# TeensyCtrlr.net
KiCad netlist of a schematic drawn in EAGLE
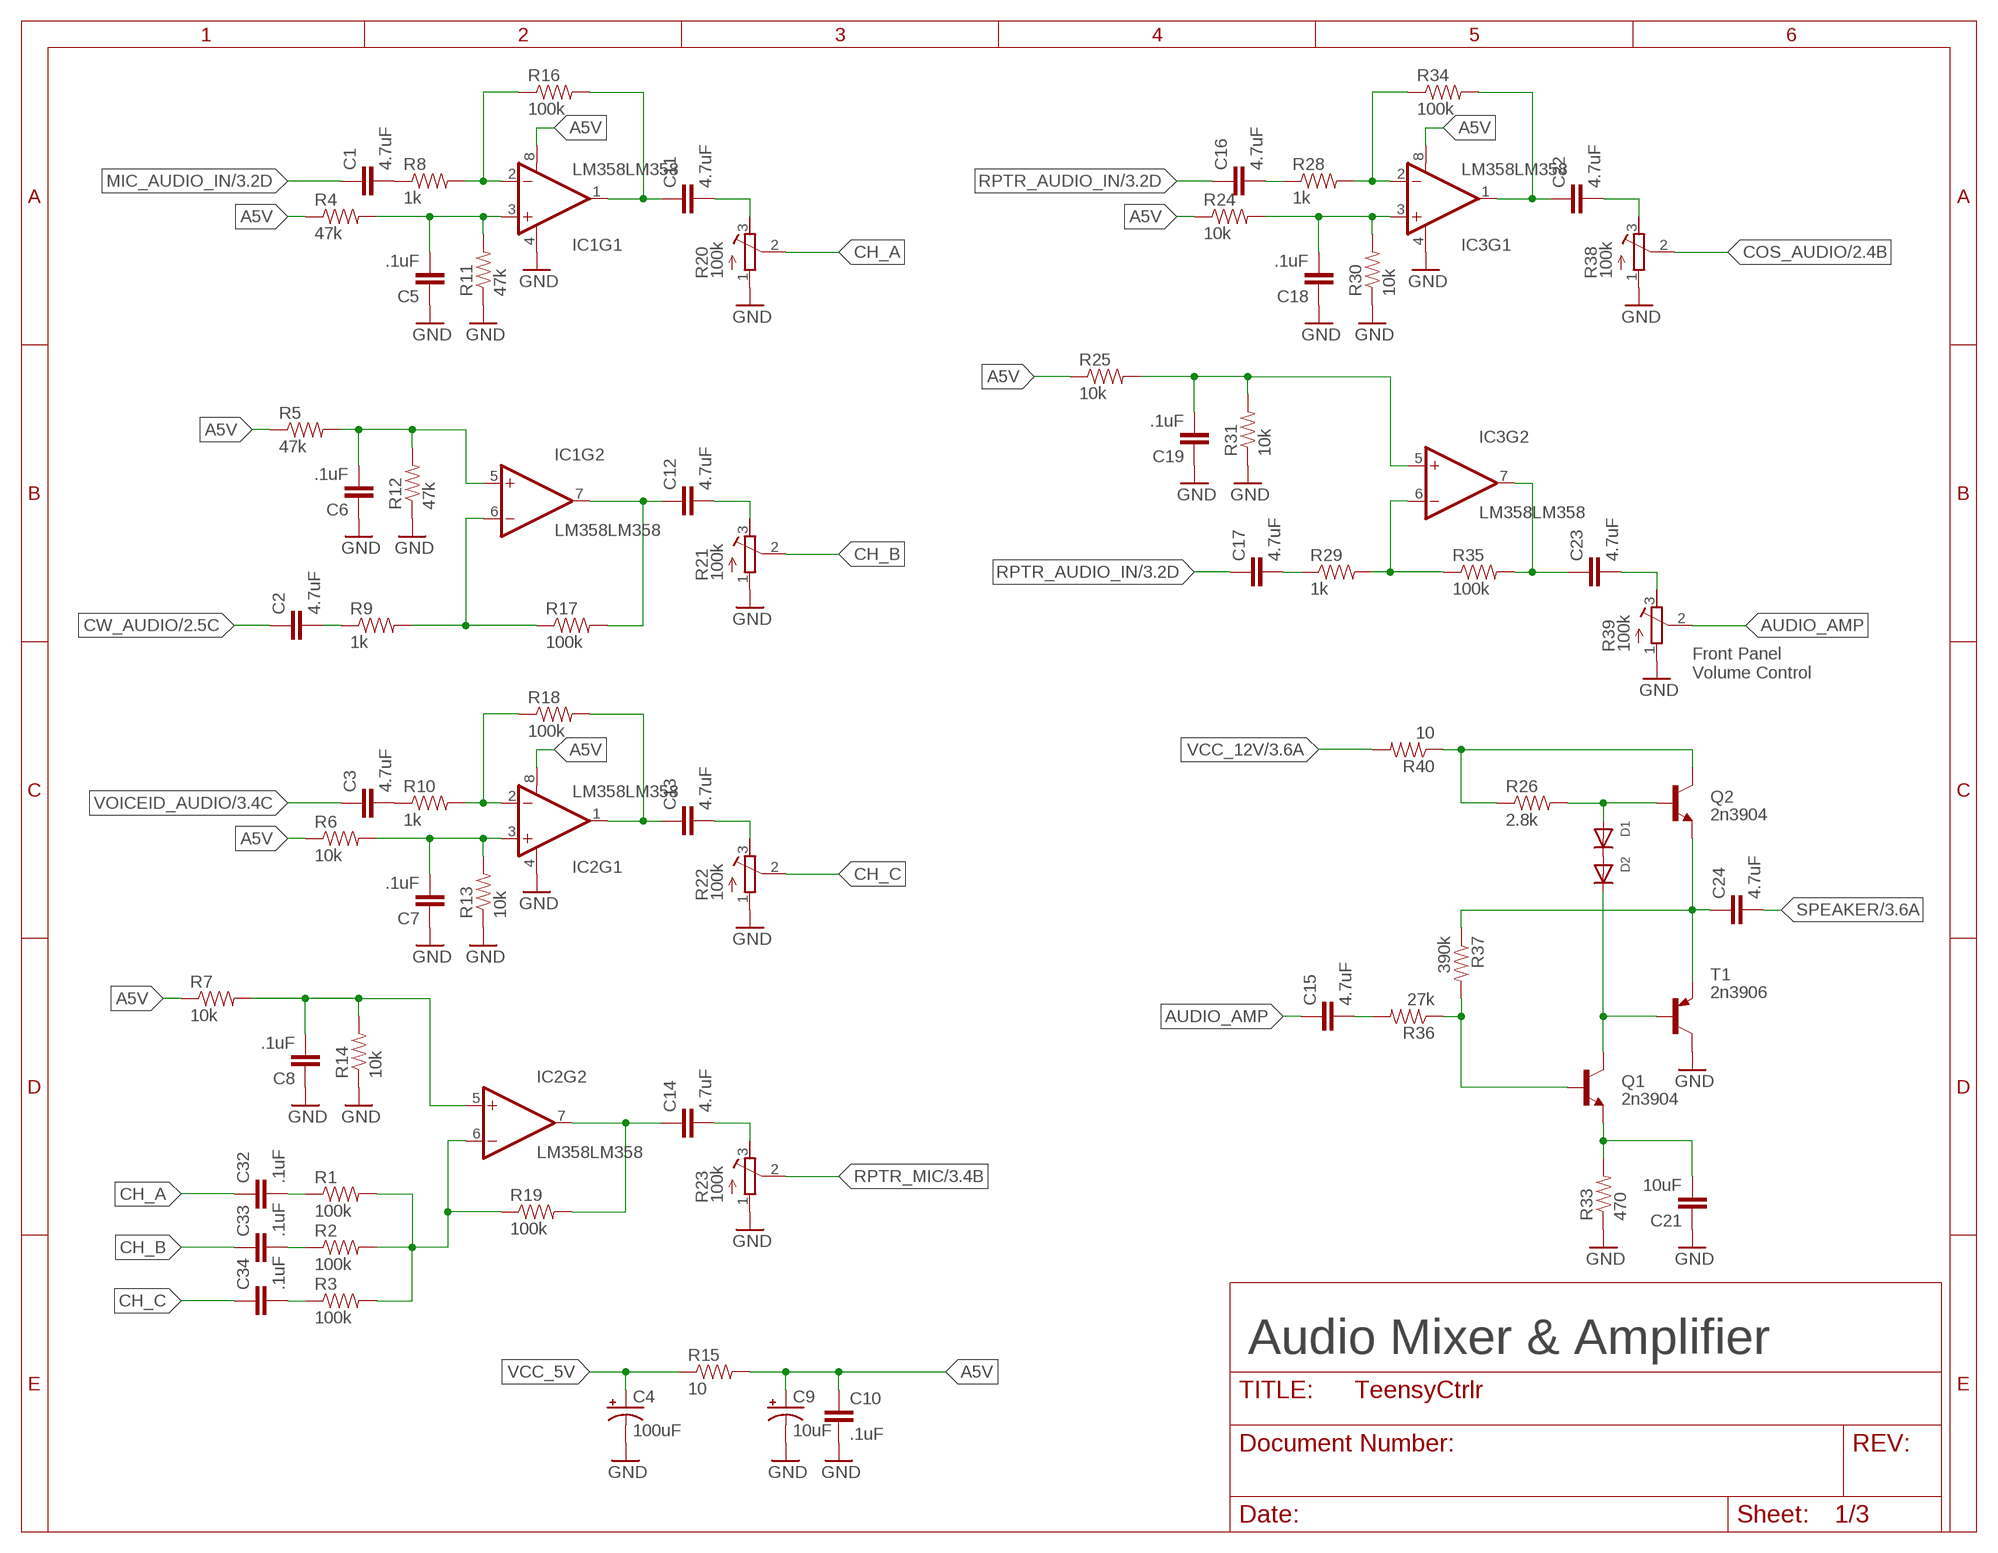
[diagram p0: schematic, sheet 1]
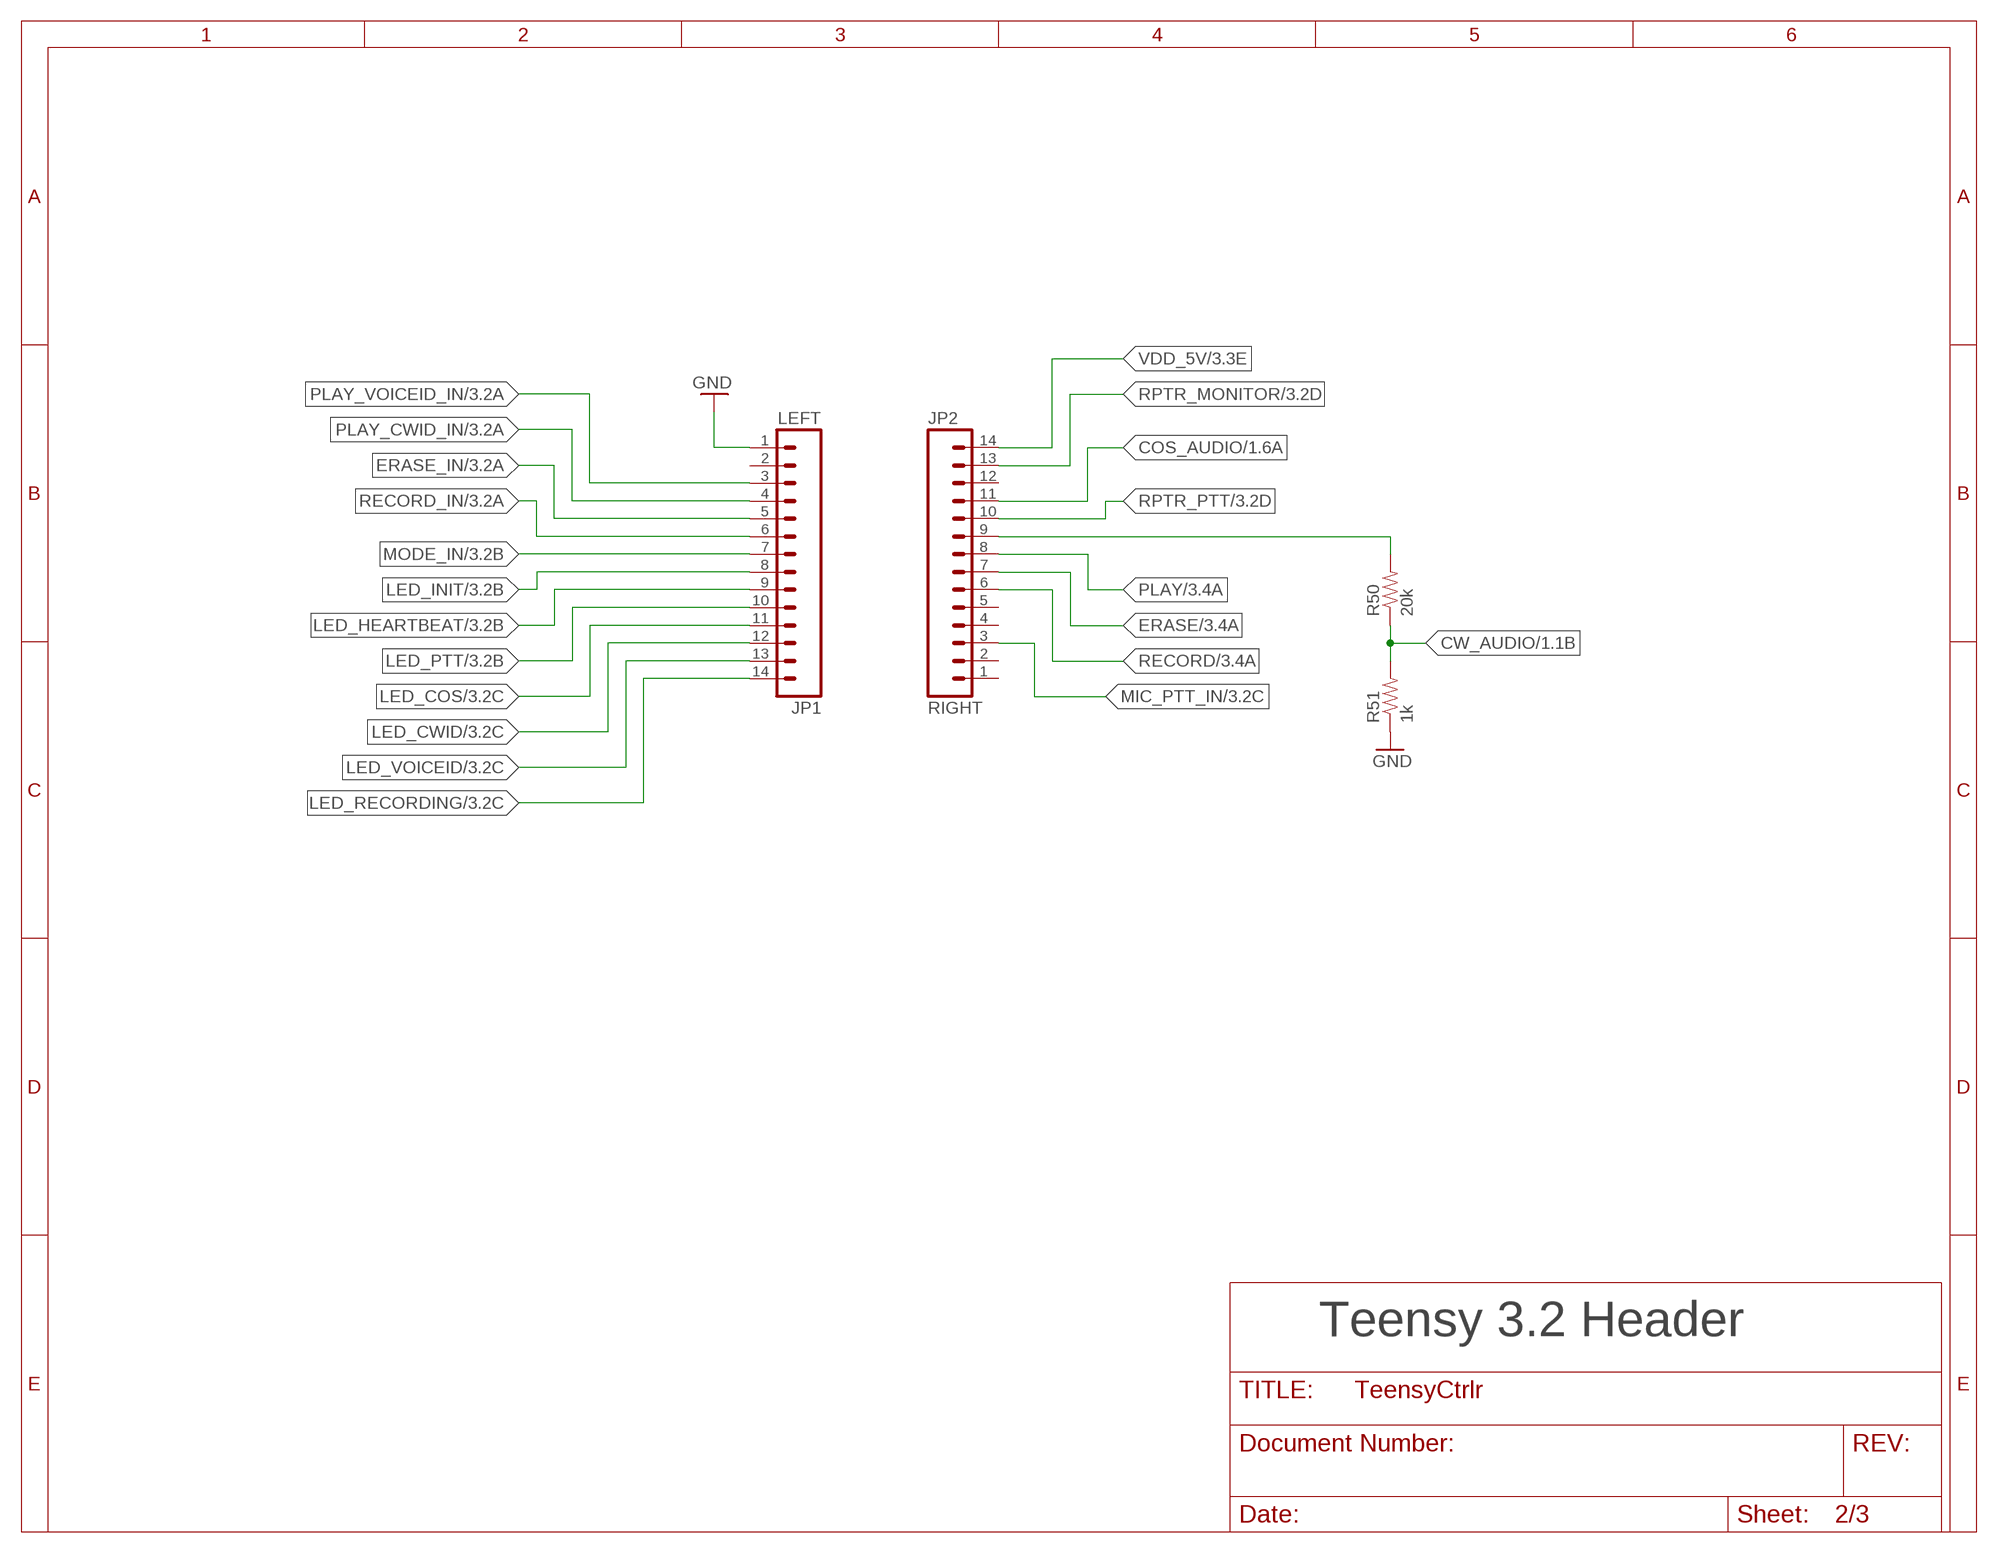
[diagram p1: schematic, sheet 2]
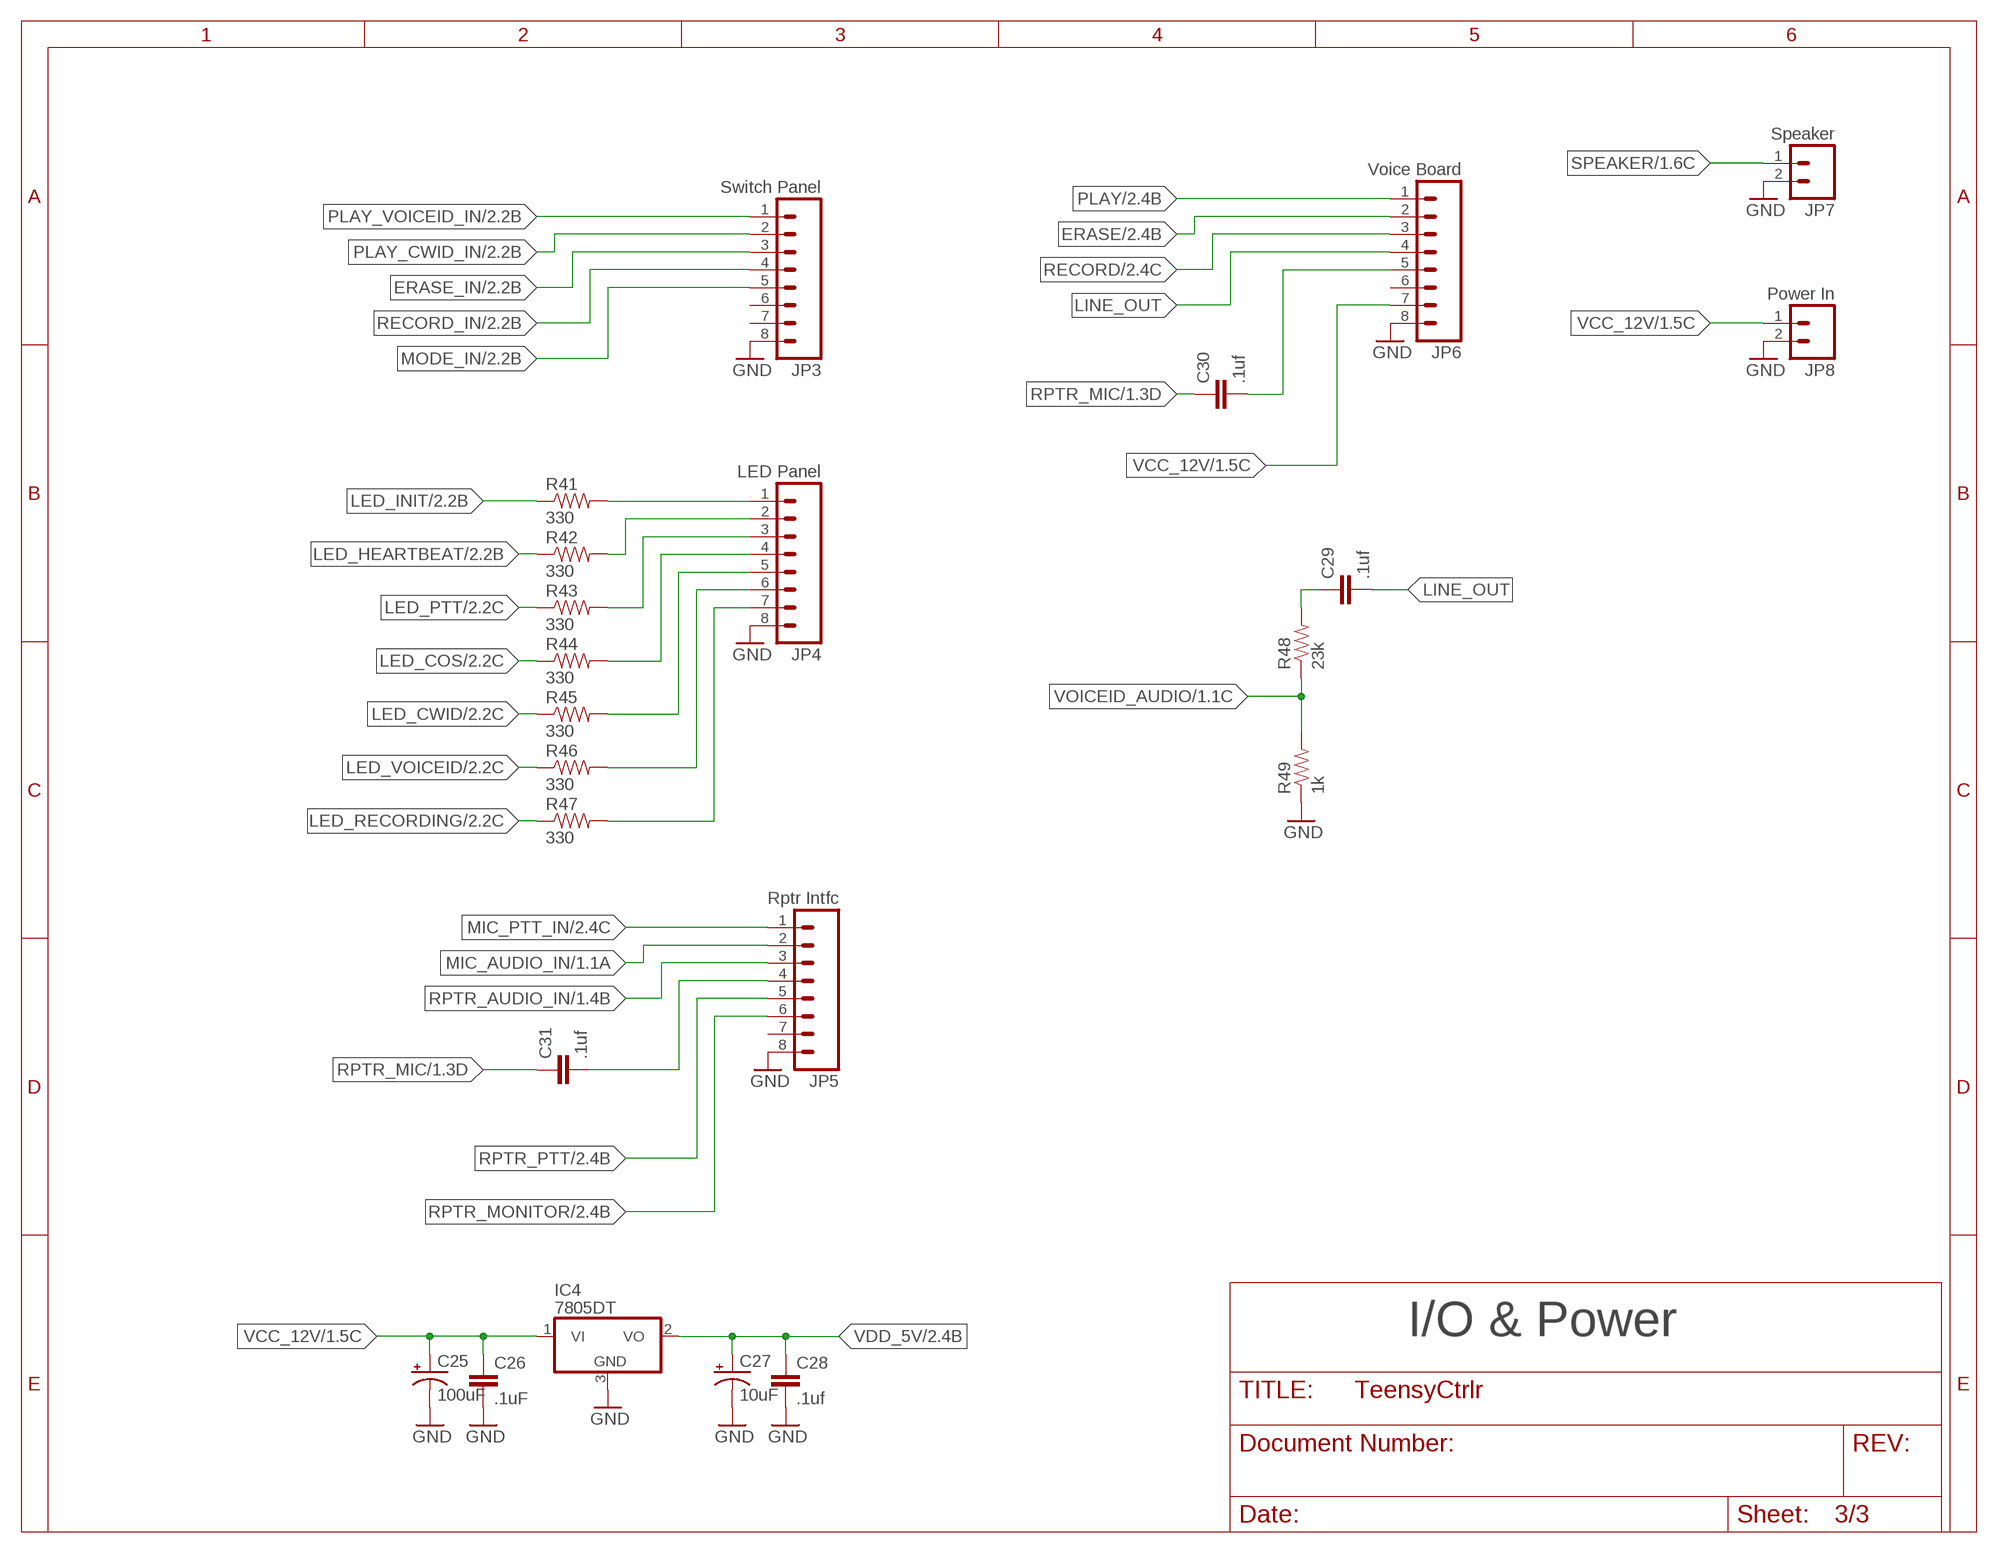
[diagram p2: schematic, sheet 3]

(export (version "E")
  (design (tool "Eeschema 10.0.6"))
  (components
    (comp (ref "C25")
      (value "100uF")
      (footprint "eagle-import:CPOL-RADIAL-1000UF-25V")
      (libsource (lib "eagle-import") (part "CAP_POLPTH4"))
    )
    (comp (ref "C26")
      (value ".1uF")
      (footprint "eagle-import:0805")
      (libsource (lib "eagle-import") (part "CAP0805"))
    )
    (comp (ref "C27")
      (value "10uF")
      (footprint "eagle-import:CPOL-RADIAL-100UF-25V")
      (libsource (lib "eagle-import") (part "CAP_POLPTH1"))
    )
    (comp (ref "C28")
      (value ".1uf")
      (footprint "eagle-import:0805")
      (libsource (lib "eagle-import") (part "CAP0805"))
    )
    (comp (ref "C29")
      (value ".1uf")
      (footprint "eagle-import:0805")
      (libsource (lib "eagle-import") (part "CAP0805"))
    )
    (comp (ref "C30")
      (value ".1uf")
      (footprint "eagle-import:0805")
      (libsource (lib "eagle-import") (part "CAP0805"))
    )
    (comp (ref "C31")
      (value ".1uf")
      (footprint "eagle-import:0805")
      (libsource (lib "eagle-import") (part "CAP0805"))
    )
    (comp (ref "IC4")
      (value "7805DT")
      (footprint "eagle-import:TO252")
      (libsource (lib "eagle-import") (part "78DT05"))
    )
    (comp (ref "JP3")
      (value "Switch Panel")
      (footprint "eagle-import:1X08_LONGPADS")
      (libsource (lib "eagle-import") (part "M08LONGPADS"))
    )
    (comp (ref "JP4")
      (value "LED Panel")
      (footprint "eagle-import:1X08_LONGPADS")
      (libsource (lib "eagle-import") (part "M08LONGPADS"))
    )
    (comp (ref "JP5")
      (value "Rptr Intfc")
      (footprint "eagle-import:1X08_LONGPADS")
      (libsource (lib "eagle-import") (part "M08LONGPADS"))
    )
    (comp (ref "JP6")
      (value "Voice Board")
      (footprint "eagle-import:1X08_LONGPADS")
      (libsource (lib "eagle-import") (part "M08LONGPADS"))
    )
    (comp (ref "JP7")
      (value "Speaker")
      (footprint "eagle-import:1X02_LONGPADS")
      (libsource (lib "eagle-import") (part "M02PTH3"))
    )
    (comp (ref "JP8")
      (value "Power In")
      (footprint "eagle-import:1X02_LONGPADS")
      (libsource (lib "eagle-import") (part "M02PTH3"))
    )
    (comp (ref "R41")
      (value "330")
      (footprint "eagle-import:0805")
      (libsource (lib "eagle-import") (part "RESISTOR0805-RES"))
    )
    (comp (ref "R42")
      (value "330")
      (footprint "eagle-import:0805")
      (libsource (lib "eagle-import") (part "RESISTOR0805-RES"))
    )
    (comp (ref "R43")
      (value "330")
      (footprint "eagle-import:0805")
      (libsource (lib "eagle-import") (part "RESISTOR0805-RES"))
    )
    (comp (ref "R44")
      (value "330")
      (footprint "eagle-import:0805")
      (libsource (lib "eagle-import") (part "RESISTOR0805-RES"))
    )
    (comp (ref "R45")
      (value "330")
      (footprint "eagle-import:0805")
      (libsource (lib "eagle-import") (part "RESISTOR0805-RES"))
    )
    (comp (ref "R46")
      (value "330")
      (footprint "eagle-import:0805")
      (libsource (lib "eagle-import") (part "RESISTOR0805-RES"))
    )
    (comp (ref "R47")
      (value "330")
      (footprint "eagle-import:0805")
      (libsource (lib "eagle-import") (part "RESISTOR0805-RES"))
    )
    (comp (ref "R48")
      (value "23k")
      (footprint "eagle-import:0805")
      (libsource (lib "eagle-import") (part "RESISTOR0805-RES"))
    )
    (comp (ref "R49")
      (value "1k")
      (footprint "eagle-import:0805")
      (libsource (lib "eagle-import") (part "RESISTOR0805-RES"))
    )
    (comp (ref "JP1")
      (value "LEFT")
      (footprint "eagle-import:1X14-LONGPADS")
      (libsource (lib "eagle-import") (part "M14LONGPADS"))
    )
    (comp (ref "JP2")
      (value "RIGHT")
      (footprint "eagle-import:1X14-LONGPADS")
      (libsource (lib "eagle-import") (part "M14LONGPADS"))
    )
    (comp (ref "R50")
      (value "20k")
      (footprint "eagle-import:0805")
      (libsource (lib "eagle-import") (part "RESISTOR0805-RES"))
    )
    (comp (ref "R51")
      (value "1k")
      (footprint "eagle-import:0805")
      (libsource (lib "eagle-import") (part "RESISTOR0805-RES"))
    )
    (comp (ref "C1")
      (value "4.7uF")
      (footprint "eagle-import:CAP-PTH-SMALL2")
      (libsource (lib "eagle-import") (part "CAPPTH2"))
    )
    (comp (ref "C2")
      (value "4.7uF")
      (footprint "eagle-import:CAP-PTH-SMALL2")
      (libsource (lib "eagle-import") (part "CAPPTH2"))
    )
    (comp (ref "C3")
      (value "4.7uF")
      (footprint "eagle-import:CAP-PTH-SMALL2")
      (libsource (lib "eagle-import") (part "CAPPTH2"))
    )
    (comp (ref "C4")
      (value "100uF")
      (footprint "eagle-import:CPOL-RADIAL-10UF-25V")
      (libsource (lib "eagle-import") (part "CAP_POLPTH2"))
    )
    (comp (ref "C5")
      (value ".1uF")
      (footprint "eagle-import:0805")
      (libsource (lib "eagle-import") (part "CAP0805"))
    )
    (comp (ref "C6")
      (value ".1uF")
      (footprint "eagle-import:0805")
      (libsource (lib "eagle-import") (part "CAP0805"))
    )
    (comp (ref "C7")
      (value ".1uF")
      (footprint "eagle-import:0805")
      (libsource (lib "eagle-import") (part "CAP0805"))
    )
    (comp (ref "C8")
      (value ".1uF")
      (footprint "eagle-import:0805")
      (libsource (lib "eagle-import") (part "CAP0805"))
    )
    (comp (ref "C9")
      (value "10uF")
      (footprint "eagle-import:CPOL-RADIAL-100UF-25V")
      (libsource (lib "eagle-import") (part "CAP_POLPTH1"))
    )
    (comp (ref "C10")
      (value ".1uF")
      (footprint "eagle-import:0805")
      (libsource (lib "eagle-import") (part "CAP0805"))
    )
    (comp (ref "C11")
      (value "4.7uF")
      (footprint "eagle-import:CAP-PTH-SMALL2")
      (libsource (lib "eagle-import") (part "CAPPTH2"))
    )
    (comp (ref "C12")
      (value "4.7uF")
      (footprint "eagle-import:CAP-PTH-SMALL2")
      (libsource (lib "eagle-import") (part "CAPPTH2"))
    )
    (comp (ref "C13")
      (value "4.7uF")
      (footprint "eagle-import:CAP-PTH-SMALL2")
      (libsource (lib "eagle-import") (part "CAPPTH2"))
    )
    (comp (ref "C14")
      (value "4.7uF")
      (footprint "eagle-import:CAP-PTH-SMALL2")
      (libsource (lib "eagle-import") (part "CAPPTH2"))
    )
    (comp (ref "C15")
      (value "4.7uF")
      (footprint "eagle-import:CAP-PTH-SMALL")
      (libsource (lib "eagle-import") (part "CAPPTH"))
    )
    (comp (ref "C16")
      (value "4.7uF")
      (footprint "eagle-import:CAP-PTH-SMALL2")
      (libsource (lib "eagle-import") (part "CAPPTH2"))
    )
    (comp (ref "C17")
      (value "4.7uF")
      (footprint "eagle-import:CAP-PTH-SMALL2")
      (libsource (lib "eagle-import") (part "CAPPTH2"))
    )
    (comp (ref "C18")
      (value ".1uF")
      (footprint "eagle-import:0805")
      (libsource (lib "eagle-import") (part "CAP0805"))
    )
    (comp (ref "C19")
      (value ".1uF")
      (footprint "eagle-import:0805")
      (libsource (lib "eagle-import") (part "CAP0805"))
    )
    (comp (ref "C21")
      (value "10uF")
      (footprint "eagle-import:CAP-PTH-SMALL")
      (libsource (lib "eagle-import") (part "CAPPTH"))
    )
    (comp (ref "C22")
      (value "4.7uF")
      (footprint "eagle-import:CAP-PTH-SMALL2")
      (libsource (lib "eagle-import") (part "CAPPTH2"))
    )
    (comp (ref "C23")
      (value "4.7uF")
      (footprint "eagle-import:CAP-PTH-SMALL2")
      (libsource (lib "eagle-import") (part "CAPPTH2"))
    )
    (comp (ref "C24")
      (value "4.7uF")
      (footprint "eagle-import:CAP-PTH-SMALL")
      (libsource (lib "eagle-import") (part "CAPPTH"))
    )
    (comp (ref "C32")
      (value ".1uF")
      (footprint "eagle-import:0805")
      (libsource (lib "eagle-import") (part "CAP0805"))
    )
    (comp (ref "C33")
      (value ".1uF")
      (footprint "eagle-import:0805")
      (libsource (lib "eagle-import") (part "CAP0805"))
    )
    (comp (ref "C34")
      (value ".1uF")
      (footprint "eagle-import:0805")
      (libsource (lib "eagle-import") (part "CAP0805"))
    )
    (comp (ref "D1")
      (value "DIODEDO-1N4148")
      (footprint "eagle-import:DO-1N4148")
      (libsource (lib "eagle-import") (part "DIODEDO-1N4148"))
    )
    (comp (ref "D2")
      (value "DIODEDO-1N4148")
      (footprint "eagle-import:DO-1N4148")
      (libsource (lib "eagle-import") (part "DIODEDO-1N4148"))
    )
    (comp (ref "IC1")
      (value "LM358LM358")
      (footprint "eagle-import:SOIC8")
      (libsource (lib "eagle-import") (part "LM358LM358"))
    )
    (comp (ref "IC2")
      (value "LM358LM358")
      (footprint "eagle-import:SOIC8")
      (libsource (lib "eagle-import") (part "LM358LM358"))
    )
    (comp (ref "IC3")
      (value "LM358LM358")
      (footprint "eagle-import:SOIC8")
      (libsource (lib "eagle-import") (part "LM358LM358"))
    )
    (comp (ref "Q1")
      (value "2n3904")
      (footprint "eagle-import:TO-92-AMMO")
      (libsource (lib "eagle-import") (part "TRANSISTOR_NPNTO-92-AMMO"))
    )
    (comp (ref "Q2")
      (value "2n3904")
      (footprint "eagle-import:TO-92-AMMO")
      (libsource (lib "eagle-import") (part "TRANSISTOR_NPNTO-92-AMMO"))
    )
    (comp (ref "R1")
      (value "100k")
      (footprint "eagle-import:0805")
      (libsource (lib "eagle-import") (part "RESISTOR0805-RES"))
    )
    (comp (ref "R2")
      (value "100k")
      (footprint "eagle-import:0805")
      (libsource (lib "eagle-import") (part "RESISTOR0805-RES"))
    )
    (comp (ref "R3")
      (value "100k")
      (footprint "eagle-import:0805")
      (libsource (lib "eagle-import") (part "RESISTOR0805-RES"))
    )
    (comp (ref "R4")
      (value "47k")
      (footprint "eagle-import:0805")
      (libsource (lib "eagle-import") (part "RESISTOR0805-RES"))
    )
    (comp (ref "R5")
      (value "47k")
      (footprint "eagle-import:0805")
      (libsource (lib "eagle-import") (part "RESISTOR0805-RES"))
    )
    (comp (ref "R6")
      (value "10k")
      (footprint "eagle-import:0805")
      (libsource (lib "eagle-import") (part "RESISTOR0805-RES"))
    )
    (comp (ref "R7")
      (value "10k")
      (footprint "eagle-import:0805")
      (libsource (lib "eagle-import") (part "RESISTOR0805-RES"))
    )
    (comp (ref "R8")
      (value "1k")
      (footprint "eagle-import:0805")
      (libsource (lib "eagle-import") (part "RESISTOR0805-RES"))
    )
    (comp (ref "R9")
      (value "1k")
      (footprint "eagle-import:0805")
      (libsource (lib "eagle-import") (part "RESISTOR0805-RES"))
    )
    (comp (ref "R10")
      (value "1k")
      (footprint "eagle-import:0805")
      (libsource (lib "eagle-import") (part "RESISTOR0805-RES"))
    )
    (comp (ref "R11")
      (value "47k")
      (footprint "eagle-import:0805")
      (libsource (lib "eagle-import") (part "RESISTOR0805-RES"))
    )
    (comp (ref "R12")
      (value "47k")
      (footprint "eagle-import:0805")
      (libsource (lib "eagle-import") (part "RESISTOR0805-RES"))
    )
    (comp (ref "R13")
      (value "10k")
      (footprint "eagle-import:0805")
      (libsource (lib "eagle-import") (part "RESISTOR0805-RES"))
    )
    (comp (ref "R14")
      (value "10k")
      (footprint "eagle-import:0805")
      (libsource (lib "eagle-import") (part "RESISTOR0805-RES"))
    )
    (comp (ref "R15")
      (value "10")
      (footprint "eagle-import:0805")
      (libsource (lib "eagle-import") (part "RESISTOR0805-RES"))
    )
    (comp (ref "R16")
      (value "100k")
      (footprint "eagle-import:0805")
      (libsource (lib "eagle-import") (part "RESISTOR0805-RES"))
    )
    (comp (ref "R17")
      (value "100k")
      (footprint "eagle-import:0805")
      (libsource (lib "eagle-import") (part "RESISTOR0805-RES"))
    )
    (comp (ref "R18")
      (value "100k")
      (footprint "eagle-import:0805")
      (libsource (lib "eagle-import") (part "RESISTOR0805-RES"))
    )
    (comp (ref "R19")
      (value "100k")
      (footprint "eagle-import:0805")
      (libsource (lib "eagle-import") (part "RESISTOR0805-RES"))
    )
    (comp (ref "R20")
      (value "100k")
      (footprint "eagle-import:RTRIM3339P")
      (libsource (lib "eagle-import") (part "R-TRIMM3339P"))
    )
    (comp (ref "R21")
      (value "100k")
      (footprint "eagle-import:RTRIM3339P")
      (libsource (lib "eagle-import") (part "R-TRIMM3339P"))
    )
    (comp (ref "R22")
      (value "100k")
      (footprint "eagle-import:RTRIM3339P")
      (libsource (lib "eagle-import") (part "R-TRIMM3339P"))
    )
    (comp (ref "R23")
      (value "100k")
      (footprint "eagle-import:RTRIM3339P")
      (libsource (lib "eagle-import") (part "R-TRIMM3339P"))
    )
    (comp (ref "R24")
      (value "10k")
      (footprint "eagle-import:0805")
      (libsource (lib "eagle-import") (part "RESISTOR0805-RES"))
    )
    (comp (ref "R25")
      (value "10k")
      (footprint "eagle-import:0805")
      (libsource (lib "eagle-import") (part "RESISTOR0805-RES"))
    )
    (comp (ref "R26")
      (value "2.8k")
      (footprint "eagle-import:0805")
      (libsource (lib "eagle-import") (part "RESISTOR0805-RES"))
    )
    (comp (ref "R28")
      (value "1k")
      (footprint "eagle-import:0805")
      (libsource (lib "eagle-import") (part "RESISTOR0805-RES"))
    )
    (comp (ref "R29")
      (value "1k")
      (footprint "eagle-import:0805")
      (libsource (lib "eagle-import") (part "RESISTOR0805-RES"))
    )
    (comp (ref "R30")
      (value "10k")
      (footprint "eagle-import:0805")
      (libsource (lib "eagle-import") (part "RESISTOR0805-RES"))
    )
    (comp (ref "R31")
      (value "10k")
      (footprint "eagle-import:0805")
      (libsource (lib "eagle-import") (part "RESISTOR0805-RES"))
    )
    (comp (ref "R33")
      (value "470")
      (footprint "eagle-import:0805")
      (libsource (lib "eagle-import") (part "RESISTOR0805-RES"))
    )
    (comp (ref "R34")
      (value "100k")
      (footprint "eagle-import:0805")
      (libsource (lib "eagle-import") (part "RESISTOR0805-RES"))
    )
    (comp (ref "R35")
      (value "100k")
      (footprint "eagle-import:0805")
      (libsource (lib "eagle-import") (part "RESISTOR0805-RES"))
    )
    (comp (ref "R36")
      (value "27k")
      (footprint "eagle-import:0805")
      (libsource (lib "eagle-import") (part "RESISTOR0805-RES"))
    )
    (comp (ref "R37")
      (value "390k")
      (footprint "eagle-import:0805")
      (libsource (lib "eagle-import") (part "RESISTOR0805-RES"))
    )
    (comp (ref "R38")
      (value "100k")
      (footprint "eagle-import:RTRIM3339P")
      (libsource (lib "eagle-import") (part "R-TRIMM3339P"))
    )
    (comp (ref "R39")
      (value "100k")
      (footprint "eagle-import:RTRIM3339P")
      (libsource (lib "eagle-import") (part "R-TRIMM3339P"))
    )
    (comp (ref "R40")
      (value "10")
      (footprint "eagle-import:0805")
      (libsource (lib "eagle-import") (part "RESISTOR0805-RES"))
    )
    (comp (ref "T1")
      (value "2n3906")
      (footprint "eagle-import:TO92-EBC")
      (libsource (lib "eagle-import") (part "-PNP-TO92-EBCBC328-25"))
    )
  )
  (nets
    (net (code "1") (name "A5V") (class "Default")
      (node (ref "C10") (pin "1") (pinfunction "1_1") (pintype "passive"))
      (node (ref "C9") (pin "1") (pinfunction "+_1") (pintype "passive"))
      (node (ref "IC1") (pin "8") (pinfunction "V+_8") (pintype "power_in"))
      (node (ref "IC2") (pin "8") (pinfunction "V+_8") (pintype "power_in"))
      (node (ref "IC3") (pin "8") (pinfunction "V+_8") (pintype "power_in"))
      (node (ref "R15") (pin "2") (pinfunction "2_2") (pintype "passive"))
      (node (ref "R24") (pin "1") (pinfunction "1_1") (pintype "passive"))
      (node (ref "R25") (pin "1") (pinfunction "1_1") (pintype "passive"))
      (node (ref "R4") (pin "1") (pinfunction "1_1") (pintype "passive"))
      (node (ref "R5") (pin "1") (pinfunction "1_1") (pintype "passive"))
      (node (ref "R6") (pin "1") (pinfunction "1_1") (pintype "passive"))
      (node (ref "R7") (pin "1") (pinfunction "1_1") (pintype "passive"))
    )
    (net (code "2") (name "AUDIO_AMP") (class "Default")
      (node (ref "C15") (pin "1") (pinfunction "1_1") (pintype "passive"))
      (node (ref "R39") (pin "2") (pinfunction "S_2") (pintype "passive"))
    )
    (net (code "3") (name "CH_A") (class "Default")
      (node (ref "C32") (pin "1") (pinfunction "1_1") (pintype "passive"))
      (node (ref "R20") (pin "2") (pinfunction "S_2") (pintype "passive"))
    )
    (net (code "4") (name "CH_B") (class "Default")
      (node (ref "C33") (pin "1") (pinfunction "1_1") (pintype "passive"))
      (node (ref "R21") (pin "2") (pinfunction "S_2") (pintype "passive"))
    )
    (net (code "5") (name "CH_C") (class "Default")
      (node (ref "C34") (pin "1") (pinfunction "1_1") (pintype "passive"))
      (node (ref "R22") (pin "2") (pinfunction "S_2") (pintype "passive"))
    )
    (net (code "6") (name "COS_AUDIO") (class "Default")
      (node (ref "JP2") (pin "11") (pinfunction "11_11") (pintype "passive"))
      (node (ref "R38") (pin "2") (pinfunction "S_2") (pintype "passive"))
    )
    (net (code "7") (name "CW_AUDIO") (class "Default")
      (node (ref "C2") (pin "1") (pinfunction "1_1") (pintype "passive"))
      (node (ref "R50") (pin "1") (pinfunction "1_1") (pintype "passive"))
      (node (ref "R51") (pin "2") (pinfunction "2_2") (pintype "passive"))
    )
    (net (code "8") (name "ERASE") (class "Default")
      (node (ref "JP2") (pin "7") (pinfunction "7_7") (pintype "passive"))
      (node (ref "JP6") (pin "2") (pinfunction "2_2") (pintype "passive"))
    )
    (net (code "9") (name "ERASE_IN") (class "Default")
      (node (ref "JP1") (pin "5") (pinfunction "5_5") (pintype "passive"))
      (node (ref "JP3") (pin "3") (pinfunction "3_3") (pintype "passive"))
    )
    (net (code "10") (name "GND") (class "Default")
      (node (ref "C10") (pin "2") (pinfunction "2_2") (pintype "passive"))
      (node (ref "C18") (pin "1") (pinfunction "1_1") (pintype "passive"))
      (node (ref "C19") (pin "1") (pinfunction "1_1") (pintype "passive"))
      (node (ref "C21") (pin "1") (pinfunction "1_1") (pintype "passive"))
      (node (ref "C25") (pin "-") (pinfunction "-_-") (pintype "passive"))
      (node (ref "C26") (pin "2") (pinfunction "2_2") (pintype "passive"))
      (node (ref "C27") (pin "2") (pinfunction "-_2") (pintype "passive"))
      (node (ref "C28") (pin "2") (pinfunction "2_2") (pintype "passive"))
      (node (ref "C4") (pin "2") (pinfunction "-_2") (pintype "passive"))
      (node (ref "C5") (pin "1") (pinfunction "1_1") (pintype "passive"))
      (node (ref "C6") (pin "1") (pinfunction "1_1") (pintype "passive"))
      (node (ref "C7") (pin "1") (pinfunction "1_1") (pintype "passive"))
      (node (ref "C8") (pin "1") (pinfunction "1_1") (pintype "passive"))
      (node (ref "C9") (pin "2") (pinfunction "-_2") (pintype "passive"))
      (node (ref "IC1") (pin "4") (pinfunction "V-_4") (pintype "power_in"))
      (node (ref "IC2") (pin "4") (pinfunction "V-_4") (pintype "power_in"))
      (node (ref "IC3") (pin "4") (pinfunction "V-_4") (pintype "power_in"))
      (node (ref "IC4") (pin "3") (pinfunction "GND_3") (pintype "passive"))
      (node (ref "JP1") (pin "1") (pinfunction "1_1") (pintype "passive"))
      (node (ref "JP3") (pin "8") (pinfunction "8_8") (pintype "passive"))
      (node (ref "JP4") (pin "8") (pinfunction "8_8") (pintype "passive"))
      (node (ref "JP5") (pin "8") (pinfunction "8_8") (pintype "passive"))
      (node (ref "JP6") (pin "8") (pinfunction "8_8") (pintype "passive"))
      (node (ref "JP7") (pin "2") (pinfunction "2_2") (pintype "passive"))
      (node (ref "JP8") (pin "2") (pinfunction "2_2") (pintype "passive"))
      (node (ref "R11") (pin "1") (pinfunction "1_1") (pintype "passive"))
      (node (ref "R12") (pin "1") (pinfunction "1_1") (pintype "passive"))
      (node (ref "R13") (pin "1") (pinfunction "1_1") (pintype "passive"))
      (node (ref "R14") (pin "1") (pinfunction "1_1") (pintype "passive"))
      (node (ref "R20") (pin "1") (pinfunction "A_1") (pintype "passive"))
      (node (ref "R21") (pin "1") (pinfunction "A_1") (pintype "passive"))
      (node (ref "R22") (pin "1") (pinfunction "A_1") (pintype "passive"))
      (node (ref "R23") (pin "1") (pinfunction "A_1") (pintype "passive"))
      (node (ref "R30") (pin "1") (pinfunction "1_1") (pintype "passive"))
      (node (ref "R31") (pin "1") (pinfunction "1_1") (pintype "passive"))
      (node (ref "R33") (pin "1") (pinfunction "1_1") (pintype "passive"))
      (node (ref "R38") (pin "1") (pinfunction "A_1") (pintype "passive"))
      (node (ref "R39") (pin "1") (pinfunction "A_1") (pintype "passive"))
      (node (ref "R49") (pin "1") (pinfunction "1_1") (pintype "passive"))
      (node (ref "R51") (pin "1") (pinfunction "1_1") (pintype "passive"))
      (node (ref "T1") (pin "C") (pinfunction "C_C") (pintype "passive"))
    )
    (net (code "11") (name "LED_COS") (class "Default")
      (node (ref "JP1") (pin "11") (pinfunction "11_11") (pintype "passive"))
      (node (ref "R44") (pin "1") (pinfunction "1_1") (pintype "passive"))
    )
    (net (code "12") (name "LED_CWID") (class "Default")
      (node (ref "JP1") (pin "12") (pinfunction "12_12") (pintype "passive"))
      (node (ref "R45") (pin "1") (pinfunction "1_1") (pintype "passive"))
    )
    (net (code "13") (name "LED_HEARTBEAT") (class "Default")
      (node (ref "JP1") (pin "9") (pinfunction "9_9") (pintype "passive"))
      (node (ref "R42") (pin "1") (pinfunction "1_1") (pintype "passive"))
    )
    (net (code "14") (name "LED_INIT") (class "Default")
      (node (ref "JP1") (pin "8") (pinfunction "8_8") (pintype "passive"))
      (node (ref "R41") (pin "1") (pinfunction "1_1") (pintype "passive"))
    )
    (net (code "15") (name "LED_PTT") (class "Default")
      (node (ref "JP1") (pin "10") (pinfunction "10_10") (pintype "passive"))
      (node (ref "R43") (pin "1") (pinfunction "1_1") (pintype "passive"))
    )
    (net (code "16") (name "LED_RECORDING") (class "Default")
      (node (ref "JP1") (pin "14") (pinfunction "14_14") (pintype "passive"))
      (node (ref "R47") (pin "1") (pinfunction "1_1") (pintype "passive"))
    )
    (net (code "17") (name "LED_VOICEID") (class "Default")
      (node (ref "JP1") (pin "13") (pinfunction "13_13") (pintype "passive"))
      (node (ref "R46") (pin "1") (pinfunction "1_1") (pintype "passive"))
    )
    (net (code "18") (name "LINE_OUT") (class "Default")
      (node (ref "C29") (pin "2") (pinfunction "2_2") (pintype "passive"))
      (node (ref "JP6") (pin "4") (pinfunction "4_4") (pintype "passive"))
    )
    (net (code "19") (name "MIC_AUDIO_IN") (class "Default")
      (node (ref "C1") (pin "1") (pinfunction "1_1") (pintype "passive"))
      (node (ref "JP5") (pin "2") (pinfunction "2_2") (pintype "passive"))
    )
    (net (code "20") (name "MIC_PTT_IN") (class "Default")
      (node (ref "JP2") (pin "3") (pinfunction "3_3") (pintype "passive"))
      (node (ref "JP5") (pin "1") (pinfunction "1_1") (pintype "passive"))
    )
    (net (code "21") (name "MODE_IN") (class "Default")
      (node (ref "JP1") (pin "7") (pinfunction "7_7") (pintype "passive"))
      (node (ref "JP3") (pin "5") (pinfunction "5_5") (pintype "passive"))
    )
    (net (code "22") (name "Net-(C1-Pad2)") (class "Default")
      (node (ref "C1") (pin "2") (pinfunction "2_2") (pintype "passive"))
      (node (ref "R8") (pin "1") (pinfunction "1_1") (pintype "passive"))
    )
    (net (code "23") (name "Net-(C2-Pad2)") (class "Default")
      (node (ref "C2") (pin "2") (pinfunction "2_2") (pintype "passive"))
      (node (ref "R9") (pin "1") (pinfunction "1_1") (pintype "passive"))
    )
    (net (code "24") (name "Net-(C3-Pad2)") (class "Default")
      (node (ref "C3") (pin "2") (pinfunction "2_2") (pintype "passive"))
      (node (ref "R10") (pin "1") (pinfunction "1_1") (pintype "passive"))
    )
    (net (code "25") (name "Net-(C15-Pad2)") (class "Default")
      (node (ref "C15") (pin "2") (pinfunction "2_2") (pintype "passive"))
      (node (ref "R36") (pin "2") (pinfunction "2_2") (pintype "passive"))
    )
    (net (code "26") (name "Net-(C16-Pad2)") (class "Default")
      (node (ref "C16") (pin "2") (pinfunction "2_2") (pintype "passive"))
      (node (ref "R28") (pin "1") (pinfunction "1_1") (pintype "passive"))
    )
    (net (code "27") (name "Net-(C17-Pad2)") (class "Default")
      (node (ref "C17") (pin "2") (pinfunction "2_2") (pintype "passive"))
      (node (ref "R29") (pin "1") (pinfunction "1_1") (pintype "passive"))
    )
    (net (code "28") (name "Net-(C29-Pad1)") (class "Default")
      (node (ref "C29") (pin "1") (pinfunction "1_1") (pintype "passive"))
      (node (ref "R48") (pin "2") (pinfunction "2_2") (pintype "passive"))
    )
    (net (code "29") (name "Net-(C30-Pad2)") (class "Default")
      (node (ref "C30") (pin "2") (pinfunction "2_2") (pintype "passive"))
      (node (ref "JP6") (pin "5") (pinfunction "5_5") (pintype "passive"))
    )
    (net (code "30") (name "Net-(C31-Pad2)") (class "Default")
      (node (ref "C31") (pin "2") (pinfunction "2_2") (pintype "passive"))
      (node (ref "JP5") (pin "4") (pinfunction "4_4") (pintype "passive"))
    )
    (net (code "31") (name "Net-(C32-Pad2)") (class "Default")
      (node (ref "C32") (pin "2") (pinfunction "2_2") (pintype "passive"))
      (node (ref "R1") (pin "1") (pinfunction "1_1") (pintype "passive"))
    )
    (net (code "32") (name "Net-(C33-Pad2)") (class "Default")
      (node (ref "C33") (pin "2") (pinfunction "2_2") (pintype "passive"))
      (node (ref "R2") (pin "1") (pinfunction "1_1") (pintype "passive"))
    )
    (net (code "33") (name "Net-(C34-Pad2)") (class "Default")
      (node (ref "C34") (pin "2") (pinfunction "2_2") (pintype "passive"))
      (node (ref "R3") (pin "1") (pinfunction "1_1") (pintype "passive"))
    )
    (net (code "34") (name "Net-(D1-PadC)") (class "Default")
      (node (ref "D1") (pin "C") (pinfunction "C_C") (pintype "passive"))
      (node (ref "D2") (pin "A") (pinfunction "A_A") (pintype "passive"))
    )
    (net (code "35") (name "Net-(IC1A-+IN)") (class "Default")
      (node (ref "C5") (pin "2") (pinfunction "2_2") (pintype "passive"))
      (node (ref "IC1") (pin "3") (pinfunction "+IN_3") (pintype "input"))
      (node (ref "R11") (pin "2") (pinfunction "2_2") (pintype "passive"))
      (node (ref "R4") (pin "2") (pinfunction "2_2") (pintype "passive"))
    )
    (net (code "36") (name "Net-(IC1A--IN)") (class "Default")
      (node (ref "IC1") (pin "2") (pinfunction "-IN_2") (pintype "input"))
      (node (ref "R16") (pin "1") (pinfunction "1_1") (pintype "passive"))
      (node (ref "R8") (pin "2") (pinfunction "2_2") (pintype "passive"))
    )
    (net (code "37") (name "Net-(IC1A-OUT)") (class "Default")
      (node (ref "C11") (pin "1") (pinfunction "1_1") (pintype "passive"))
      (node (ref "IC1") (pin "1") (pinfunction "OUT_1") (pintype "output"))
      (node (ref "R16") (pin "2") (pinfunction "2_2") (pintype "passive"))
    )
    (net (code "38") (name "Net-(IC1B-+IN)") (class "Default")
      (node (ref "C6") (pin "2") (pinfunction "2_2") (pintype "passive"))
      (node (ref "IC1") (pin "5") (pinfunction "+IN_5") (pintype "input"))
      (node (ref "R12") (pin "2") (pinfunction "2_2") (pintype "passive"))
      (node (ref "R5") (pin "2") (pinfunction "2_2") (pintype "passive"))
    )
    (net (code "39") (name "Net-(IC1B--IN)") (class "Default")
      (node (ref "IC1") (pin "6") (pinfunction "-IN_6") (pintype "input"))
      (node (ref "R17") (pin "1") (pinfunction "1_1") (pintype "passive"))
      (node (ref "R9") (pin "2") (pinfunction "2_2") (pintype "passive"))
    )
    (net (code "40") (name "Net-(IC1B-OUT)") (class "Default")
      (node (ref "C12") (pin "1") (pinfunction "1_1") (pintype "passive"))
      (node (ref "IC1") (pin "7") (pinfunction "OUT_7") (pintype "output"))
      (node (ref "R17") (pin "2") (pinfunction "2_2") (pintype "passive"))
    )
    (net (code "41") (name "Net-(IC2A-+IN)") (class "Default")
      (node (ref "C7") (pin "2") (pinfunction "2_2") (pintype "passive"))
      (node (ref "IC2") (pin "3") (pinfunction "+IN_3") (pintype "input"))
      (node (ref "R13") (pin "2") (pinfunction "2_2") (pintype "passive"))
      (node (ref "R6") (pin "2") (pinfunction "2_2") (pintype "passive"))
    )
    (net (code "42") (name "Net-(IC2A--IN)") (class "Default")
      (node (ref "IC2") (pin "2") (pinfunction "-IN_2") (pintype "input"))
      (node (ref "R10") (pin "2") (pinfunction "2_2") (pintype "passive"))
      (node (ref "R18") (pin "1") (pinfunction "1_1") (pintype "passive"))
    )
    (net (code "43") (name "Net-(IC2A-OUT)") (class "Default")
      (node (ref "C13") (pin "1") (pinfunction "1_1") (pintype "passive"))
      (node (ref "IC2") (pin "1") (pinfunction "OUT_1") (pintype "output"))
      (node (ref "R18") (pin "2") (pinfunction "2_2") (pintype "passive"))
    )
    (net (code "44") (name "Net-(IC2B-+IN)") (class "Default")
      (node (ref "C8") (pin "2") (pinfunction "2_2") (pintype "passive"))
      (node (ref "IC2") (pin "5") (pinfunction "+IN_5") (pintype "input"))
      (node (ref "R14") (pin "2") (pinfunction "2_2") (pintype "passive"))
      (node (ref "R7") (pin "2") (pinfunction "2_2") (pintype "passive"))
    )
    (net (code "45") (name "Net-(IC2B--IN)") (class "Default")
      (node (ref "IC2") (pin "6") (pinfunction "-IN_6") (pintype "input"))
      (node (ref "R1") (pin "2") (pinfunction "2_2") (pintype "passive"))
      (node (ref "R19") (pin "1") (pinfunction "1_1") (pintype "passive"))
      (node (ref "R2") (pin "2") (pinfunction "2_2") (pintype "passive"))
      (node (ref "R3") (pin "2") (pinfunction "2_2") (pintype "passive"))
    )
    (net (code "46") (name "Net-(IC2B-OUT)") (class "Default")
      (node (ref "C14") (pin "1") (pinfunction "1_1") (pintype "passive"))
      (node (ref "IC2") (pin "7") (pinfunction "OUT_7") (pintype "output"))
      (node (ref "R19") (pin "2") (pinfunction "2_2") (pintype "passive"))
    )
    (net (code "47") (name "Net-(IC3A-+IN)") (class "Default")
      (node (ref "C18") (pin "2") (pinfunction "2_2") (pintype "passive"))
      (node (ref "IC3") (pin "3") (pinfunction "+IN_3") (pintype "input"))
      (node (ref "R24") (pin "2") (pinfunction "2_2") (pintype "passive"))
      (node (ref "R30") (pin "2") (pinfunction "2_2") (pintype "passive"))
    )
    (net (code "48") (name "Net-(IC3A--IN)") (class "Default")
      (node (ref "IC3") (pin "2") (pinfunction "-IN_2") (pintype "input"))
      (node (ref "R28") (pin "2") (pinfunction "2_2") (pintype "passive"))
      (node (ref "R34") (pin "1") (pinfunction "1_1") (pintype "passive"))
    )
    (net (code "49") (name "Net-(IC3A-OUT)") (class "Default")
      (node (ref "C22") (pin "1") (pinfunction "1_1") (pintype "passive"))
      (node (ref "IC3") (pin "1") (pinfunction "OUT_1") (pintype "output"))
      (node (ref "R34") (pin "2") (pinfunction "2_2") (pintype "passive"))
    )
    (net (code "50") (name "Net-(IC3B-+IN)") (class "Default")
      (node (ref "C19") (pin "2") (pinfunction "2_2") (pintype "passive"))
      (node (ref "IC3") (pin "5") (pinfunction "+IN_5") (pintype "input"))
      (node (ref "R25") (pin "2") (pinfunction "2_2") (pintype "passive"))
      (node (ref "R31") (pin "2") (pinfunction "2_2") (pintype "passive"))
    )
    (net (code "51") (name "Net-(IC3B--IN)") (class "Default")
      (node (ref "IC3") (pin "6") (pinfunction "-IN_6") (pintype "input"))
      (node (ref "R29") (pin "2") (pinfunction "2_2") (pintype "passive"))
      (node (ref "R35") (pin "1") (pinfunction "1_1") (pintype "passive"))
    )
    (net (code "52") (name "Net-(IC3B-OUT)") (class "Default")
      (node (ref "C23") (pin "1") (pinfunction "1_1") (pintype "passive"))
      (node (ref "IC3") (pin "7") (pinfunction "OUT_7") (pintype "output"))
      (node (ref "R35") (pin "2") (pinfunction "2_2") (pintype "passive"))
    )
    (net (code "53") (name "Net-(JP2-Pad9)") (class "Default")
      (node (ref "JP2") (pin "9") (pinfunction "9_9") (pintype "passive"))
      (node (ref "R50") (pin "2") (pinfunction "2_2") (pintype "passive"))
    )
    (net (code "54") (name "Net-(JP4-Pad1)") (class "Default")
      (node (ref "JP4") (pin "1") (pinfunction "1_1") (pintype "passive"))
      (node (ref "R41") (pin "2") (pinfunction "2_2") (pintype "passive"))
    )
    (net (code "55") (name "Net-(JP4-Pad2)") (class "Default")
      (node (ref "JP4") (pin "2") (pinfunction "2_2") (pintype "passive"))
      (node (ref "R42") (pin "2") (pinfunction "2_2") (pintype "passive"))
    )
    (net (code "56") (name "Net-(JP4-Pad3)") (class "Default")
      (node (ref "JP4") (pin "3") (pinfunction "3_3") (pintype "passive"))
      (node (ref "R43") (pin "2") (pinfunction "2_2") (pintype "passive"))
    )
    (net (code "57") (name "Net-(JP4-Pad4)") (class "Default")
      (node (ref "JP4") (pin "4") (pinfunction "4_4") (pintype "passive"))
      (node (ref "R44") (pin "2") (pinfunction "2_2") (pintype "passive"))
    )
    (net (code "58") (name "Net-(JP4-Pad5)") (class "Default")
      (node (ref "JP4") (pin "5") (pinfunction "5_5") (pintype "passive"))
      (node (ref "R45") (pin "2") (pinfunction "2_2") (pintype "passive"))
    )
    (net (code "59") (name "Net-(JP4-Pad6)") (class "Default")
      (node (ref "JP4") (pin "6") (pinfunction "6_6") (pintype "passive"))
      (node (ref "R46") (pin "2") (pinfunction "2_2") (pintype "passive"))
    )
    (net (code "60") (name "Net-(JP4-Pad7)") (class "Default")
      (node (ref "JP4") (pin "7") (pinfunction "7_7") (pintype "passive"))
      (node (ref "R47") (pin "2") (pinfunction "2_2") (pintype "passive"))
    )
    (net (code "61") (name "Net-(Q1-B)") (class "Default")
      (node (ref "Q1") (pin "2") (pinfunction "B_2") (pintype "passive"))
      (node (ref "R36") (pin "1") (pinfunction "1_1") (pintype "passive"))
      (node (ref "R37") (pin "2") (pinfunction "2_2") (pintype "passive"))
    )
    (net (code "62") (name "Net-(Q1-C)") (class "Default")
      (node (ref "D2") (pin "C") (pinfunction "C_C") (pintype "passive"))
      (node (ref "Q1") (pin "3") (pinfunction "C_3") (pintype "passive"))
      (node (ref "T1") (pin "B") (pinfunction "B_B") (pintype "passive"))
    )
    (net (code "63") (name "Net-(Q1-E)") (class "Default")
      (node (ref "C21") (pin "2") (pinfunction "2_2") (pintype "passive"))
      (node (ref "Q1") (pin "1") (pinfunction "E_1") (pintype "passive"))
      (node (ref "R33") (pin "2") (pinfunction "2_2") (pintype "passive"))
    )
    (net (code "64") (name "Net-(Q2-B)") (class "Default")
      (node (ref "D1") (pin "A") (pinfunction "A_A") (pintype "passive"))
      (node (ref "Q2") (pin "2") (pinfunction "B_2") (pintype "passive"))
      (node (ref "R26") (pin "2") (pinfunction "2_2") (pintype "passive"))
    )
    (net (code "65") (name "Net-(Q2-C)") (class "Default")
      (node (ref "Q2") (pin "3") (pinfunction "C_3") (pintype "passive"))
      (node (ref "R26") (pin "1") (pinfunction "1_1") (pintype "passive"))
      (node (ref "R40") (pin "1") (pinfunction "1_1") (pintype "passive"))
    )
    (net (code "66") (name "Net-(Q2-E)") (class "Default")
      (node (ref "C24") (pin "1") (pinfunction "1_1") (pintype "passive"))
      (node (ref "Q2") (pin "1") (pinfunction "E_1") (pintype "passive"))
      (node (ref "R37") (pin "1") (pinfunction "1_1") (pintype "passive"))
      (node (ref "T1") (pin "E") (pinfunction "E_E") (pintype "passive"))
    )
    (net (code "67") (name "Net-(R20-E)") (class "Default")
      (node (ref "C11") (pin "2") (pinfunction "2_2") (pintype "passive"))
      (node (ref "R20") (pin "3") (pinfunction "E_3") (pintype "passive"))
    )
    (net (code "68") (name "Net-(R21-E)") (class "Default")
      (node (ref "C12") (pin "2") (pinfunction "2_2") (pintype "passive"))
      (node (ref "R21") (pin "3") (pinfunction "E_3") (pintype "passive"))
    )
    (net (code "69") (name "Net-(R22-E)") (class "Default")
      (node (ref "C13") (pin "2") (pinfunction "2_2") (pintype "passive"))
      (node (ref "R22") (pin "3") (pinfunction "E_3") (pintype "passive"))
    )
    (net (code "70") (name "Net-(R23-E)") (class "Default")
      (node (ref "C14") (pin "2") (pinfunction "2_2") (pintype "passive"))
      (node (ref "R23") (pin "3") (pinfunction "E_3") (pintype "passive"))
    )
    (net (code "71") (name "Net-(R38-E)") (class "Default")
      (node (ref "C22") (pin "2") (pinfunction "2_2") (pintype "passive"))
      (node (ref "R38") (pin "3") (pinfunction "E_3") (pintype "passive"))
    )
    (net (code "72") (name "Net-(R39-E)") (class "Default")
      (node (ref "C23") (pin "2") (pinfunction "2_2") (pintype "passive"))
      (node (ref "R39") (pin "3") (pinfunction "E_3") (pintype "passive"))
    )
    (net (code "73") (name "PLAY") (class "Default")
      (node (ref "JP2") (pin "8") (pinfunction "8_8") (pintype "passive"))
      (node (ref "JP6") (pin "1") (pinfunction "1_1") (pintype "passive"))
    )
    (net (code "74") (name "PLAY_CWID_IN") (class "Default")
      (node (ref "JP1") (pin "4") (pinfunction "4_4") (pintype "passive"))
      (node (ref "JP3") (pin "2") (pinfunction "2_2") (pintype "passive"))
    )
    (net (code "75") (name "PLAY_VOICEID_IN") (class "Default")
      (node (ref "JP1") (pin "3") (pinfunction "3_3") (pintype "passive"))
      (node (ref "JP3") (pin "1") (pinfunction "1_1") (pintype "passive"))
    )
    (net (code "76") (name "RECORD") (class "Default")
      (node (ref "JP2") (pin "6") (pinfunction "6_6") (pintype "passive"))
      (node (ref "JP6") (pin "3") (pinfunction "3_3") (pintype "passive"))
    )
    (net (code "77") (name "RECORD_IN") (class "Default")
      (node (ref "JP1") (pin "6") (pinfunction "6_6") (pintype "passive"))
      (node (ref "JP3") (pin "4") (pinfunction "4_4") (pintype "passive"))
    )
    (net (code "78") (name "RPTR_AUDIO_IN") (class "Default")
      (node (ref "C16") (pin "1") (pinfunction "1_1") (pintype "passive"))
      (node (ref "C17") (pin "1") (pinfunction "1_1") (pintype "passive"))
      (node (ref "JP5") (pin "3") (pinfunction "3_3") (pintype "passive"))
    )
    (net (code "79") (name "RPTR_MIC") (class "Default")
      (node (ref "C30") (pin "1") (pinfunction "1_1") (pintype "passive"))
      (node (ref "C31") (pin "1") (pinfunction "1_1") (pintype "passive"))
      (node (ref "R23") (pin "2") (pinfunction "S_2") (pintype "passive"))
    )
    (net (code "80") (name "RPTR_MONITOR") (class "Default")
      (node (ref "JP2") (pin "13") (pinfunction "13_13") (pintype "passive"))
      (node (ref "JP5") (pin "6") (pinfunction "6_6") (pintype "passive"))
    )
    (net (code "81") (name "RPTR_PTT") (class "Default")
      (node (ref "JP2") (pin "10") (pinfunction "10_10") (pintype "passive"))
      (node (ref "JP5") (pin "5") (pinfunction "5_5") (pintype "passive"))
    )
    (net (code "82") (name "SPEAKER") (class "Default")
      (node (ref "C24") (pin "2") (pinfunction "2_2") (pintype "passive"))
      (node (ref "JP7") (pin "1") (pinfunction "1_1") (pintype "passive"))
    )
    (net (code "83") (name "VCC_5V") (class "Default")
      (node (ref "C4") (pin "1") (pinfunction "+_1") (pintype "passive"))
      (node (ref "R15") (pin "1") (pinfunction "1_1") (pintype "passive"))
    )
    (net (code "84") (name "VCC_12V") (class "Default")
      (node (ref "C25") (pin "+") (pinfunction "+_+") (pintype "passive"))
      (node (ref "C26") (pin "1") (pinfunction "1_1") (pintype "passive"))
      (node (ref "IC4") (pin "1") (pinfunction "VI_1") (pintype "input"))
      (node (ref "JP6") (pin "7") (pinfunction "7_7") (pintype "passive"))
      (node (ref "JP8") (pin "1") (pinfunction "1_1") (pintype "passive"))
      (node (ref "R40") (pin "2") (pinfunction "2_2") (pintype "passive"))
    )
    (net (code "85") (name "VDD_5V") (class "Default")
      (node (ref "C27") (pin "1") (pinfunction "+_1") (pintype "passive"))
      (node (ref "C28") (pin "1") (pinfunction "1_1") (pintype "passive"))
      (node (ref "IC4") (pin "2") (pinfunction "VO_2") (pintype "passive"))
      (node (ref "JP2") (pin "14") (pinfunction "14_14") (pintype "passive"))
    )
    (net (code "86") (name "VOICEID_AUDIO") (class "Default")
      (node (ref "C3") (pin "1") (pinfunction "1_1") (pintype "passive"))
      (node (ref "R48") (pin "1") (pinfunction "1_1") (pintype "passive"))
      (node (ref "R49") (pin "2") (pinfunction "2_2") (pintype "passive"))
    )
    (net (code "87") (name "unconnected-(JP1-Pad2)") (class "Default")
      (node (ref "JP1") (pin "2") (pinfunction "2_2") (pintype "passive"))
    )
    (net (code "88") (name "unconnected-(JP2-Pad1)") (class "Default")
      (node (ref "JP2") (pin "1") (pinfunction "1_1") (pintype "passive"))
    )
    (net (code "89") (name "unconnected-(JP2-Pad2)") (class "Default")
      (node (ref "JP2") (pin "2") (pinfunction "2_2") (pintype "passive"))
    )
    (net (code "90") (name "unconnected-(JP2-Pad4)") (class "Default")
      (node (ref "JP2") (pin "4") (pinfunction "4_4") (pintype "passive"))
    )
    (net (code "91") (name "unconnected-(JP2-Pad5)") (class "Default")
      (node (ref "JP2") (pin "5") (pinfunction "5_5") (pintype "passive"))
    )
    (net (code "92") (name "unconnected-(JP2-Pad12)") (class "Default")
      (node (ref "JP2") (pin "12") (pinfunction "12_12") (pintype "passive"))
    )
    (net (code "93") (name "unconnected-(JP3-Pad6)") (class "Default")
      (node (ref "JP3") (pin "6") (pinfunction "6_6") (pintype "passive"))
    )
    (net (code "94") (name "unconnected-(JP3-Pad7)") (class "Default")
      (node (ref "JP3") (pin "7") (pinfunction "7_7") (pintype "passive"))
    )
    (net (code "95") (name "unconnected-(JP5-Pad7)") (class "Default")
      (node (ref "JP5") (pin "7") (pinfunction "7_7") (pintype "passive"))
    )
    (net (code "96") (name "unconnected-(JP6-Pad6)") (class "Default")
      (node (ref "JP6") (pin "6") (pinfunction "6_6") (pintype "passive"))
    )
  )
)
